# HHO_DRIVE_V1.net
KiCad netlist of a schematic drawn in Altium Designer
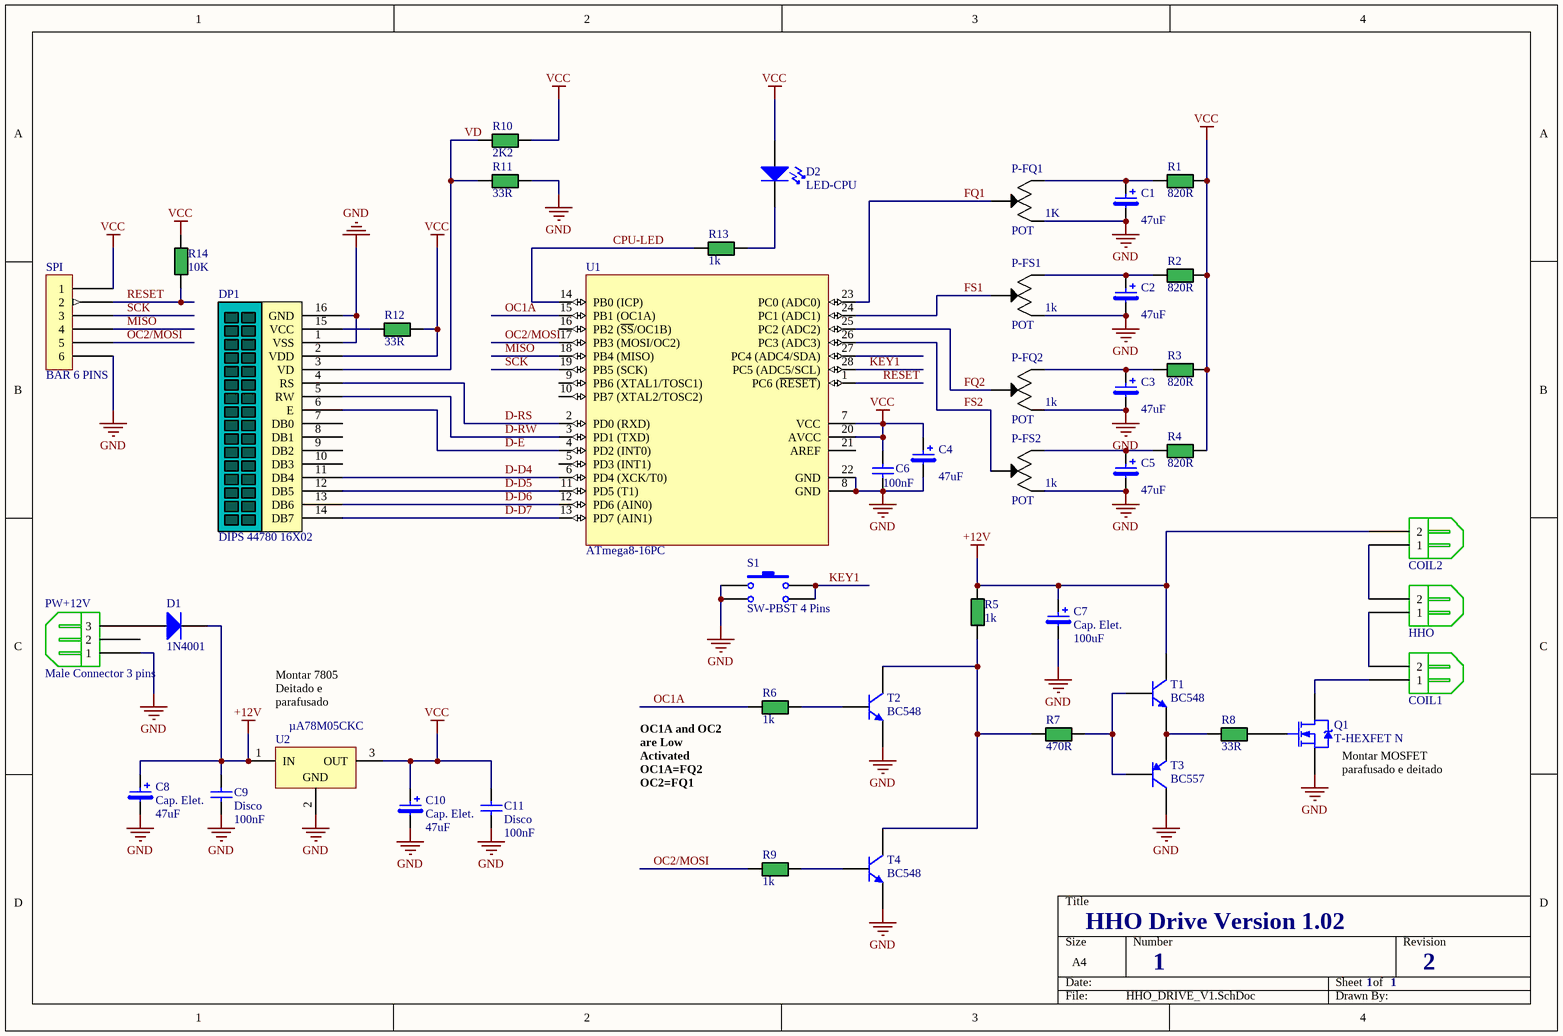
[diagram p0: HHO_DRIVE_V1.SchDoc]

(export (version "E")
  (design (tool "Eeschema 10.0.6"))
  (components
    (comp (ref "C1")
      (value "47uF")
      (footprint "CAP ELE RAD 11mm H")
      (description "Capacitor Radial Eletrolitico")
      (fields (field (name "Comment") "Cap. Elet."))
      (libsource (lib "NEPERMATH") (part "CAP_RADIAL_ELETROLITICO"))
    )
    (comp (ref "C2")
      (value "47uF")
      (footprint "CAP ELE RAD 11mm H")
      (description "Capacitor Radial Eletrolitico")
      (fields (field (name "Comment") "Cap. Elet."))
      (libsource (lib "NEPERMATH") (part "CAP_RADIAL_ELETROLITICO"))
    )
    (comp (ref "C3")
      (value "47uF")
      (footprint "CAP ELE RAD 11mm H")
      (description "Capacitor Radial Eletrolitico")
      (fields (field (name "Comment") "Cap. Elet."))
      (libsource (lib "NEPERMATH") (part "CAP_RADIAL_ELETROLITICO"))
    )
    (comp (ref "C4")
      (value "47uF")
      (footprint "CAP ELE RAD 11mm H")
      (description "Capacitor Radial Eletrolitico")
      (fields (field (name "Comment") "Cap. Elet."))
      (libsource (lib "NEPERMATH") (part "CAP_RADIAL_ELETROLITICO"))
    )
    (comp (ref "C5")
      (value "47uF")
      (footprint "CAP ELE RAD 11mm H")
      (description "Capacitor Radial Eletrolitico")
      (fields (field (name "Comment") "Cap. Elet."))
      (libsource (lib "NEPERMATH") (part "CAP_RADIAL_ELETROLITICO"))
    )
    (comp (ref "C6")
      (value "100nF")
      (footprint "CAP CER DISK 5MM")
      (description "SMD Capacitor 1210 size")
      (fields (field (name "Comment") "Disco"))
      (libsource (lib "NEPERMATH") (part "CAP_DISCO"))
    )
    (comp (ref "C7")
      (value "Cap. Elet.")
      (footprint "CAP ELE RAD 11mm H")
      (description "Capacitor Radial Eletrolitico")
      (fields (field (name "ALTIUM_VALUE") "100uF"))
      (libsource (lib "NEPERMATH") (part "CAP_RADIAL_ELETROLITICO"))
    )
    (comp (ref "C8")
      (value "Cap. Elet.")
      (footprint "CAP ELE RAD 11mm H")
      (description "Capacitor Radial Eletrolitico")
      (fields (field (name "ALTIUM_VALUE") "47uF"))
      (libsource (lib "NEPERMATH") (part "CAP_RADIAL_ELETROLITICO"))
    )
    (comp (ref "C9")
      (value "Disco")
      (footprint "CAP CER DISK 5MM")
      (description "SMD Capacitor 1210 size")
      (fields (field (name "ALTIUM_VALUE") "100nF"))
      (libsource (lib "NEPERMATH") (part "CAP_DISCO"))
    )
    (comp (ref "C10")
      (value "Cap. Elet.")
      (footprint "CAP ELE RAD 11mm H")
      (description "Capacitor Radial Eletrolitico")
      (fields (field (name "ALTIUM_VALUE") "47uF"))
      (libsource (lib "NEPERMATH") (part "CAP_RADIAL_ELETROLITICO"))
    )
    (comp (ref "C11")
      (value "Disco")
      (footprint "CAP CER DISK 5MM")
      (description "SMD Capacitor 1210 size")
      (fields (field (name "ALTIUM_VALUE") "100nF"))
      (libsource (lib "NEPERMATH") (part "CAP_DISCO"))
    )
    (comp (ref "COIL1")
      (value "Male Connector 2 pins")
      (footprint "BR102A")
      (libsource (lib "NEPERMATH") (part "Male Con 2 Pin"))
    )
    (comp (ref "COIL2")
      (value "Male Connector 2 pins")
      (footprint "BR102A")
      (libsource (lib "NEPERMATH") (part "Male Con 2 Pin"))
    )
    (comp (ref "D1")
      (value "1N4001")
      (footprint "DO-41")
      (description "1 Amp General Purpose Rectifier")
      (fields (field (name "PUBLISHER") "Altium Limited"))
      (libsource (lib "NEPERMATH") (part "Diode 1N4001"))
    )
    (comp (ref "D2")
      (value "LED-CPU")
      (footprint "LED Red 3mm")
      (description "LED")
      (libsource (lib "NEPERMATH") (part "LED"))
    )
    (comp (ref "DP1")
      (value "DIPS 44780 16X02")
      (footprint "Display 44780 16x02 com conector")
      (description "Display 44780 16x02 com conector 16 pinos")
      (libsource (lib "NEPERMATH") (part "Display 44780 16x02 com conector 16 pinos"))
    )
    (comp (ref "HHO")
      (value "Male Connector 2 pins")
      (footprint "BR102A")
      (libsource (lib "NEPERMATH") (part "Male Con 2 Pin"))
    )
    (comp (ref "P-FQ1")
      (value "POT")
      (footprint "POT 200MIL/400MIL")
      (description "Potenciometer 3 pins")
      (fields (field (name "ALTIUM_VALUE") "1K"))
      (libsource (lib "NEPERMATH") (part "POT"))
    )
    (comp (ref "P-FQ2")
      (value "POT")
      (footprint "POT 200MIL/400MIL")
      (description "Potenciometer 3 pins")
      (fields (field (name "ALTIUM_VALUE") "1k"))
      (libsource (lib "NEPERMATH") (part "POT"))
    )
    (comp (ref "P-FS1")
      (value "POT")
      (footprint "POT 200MIL/400MIL")
      (description "Potenciometer 3 pins")
      (fields (field (name "ALTIUM_VALUE") "1k"))
      (libsource (lib "NEPERMATH") (part "POT"))
    )
    (comp (ref "P-FS2")
      (value "POT")
      (footprint "POT 200MIL/400MIL")
      (description "Potenciometer 3 pins")
      (fields (field (name "ALTIUM_VALUE") "1k"))
      (libsource (lib "NEPERMATH") (part "POT"))
    )
    (comp (ref "PW+12V")
      (value "Male Connector 3 pins")
      (footprint "BR103A")
      (libsource (lib "NEPERMATH") (part "Male Con 3 Pin"))
    )
    (comp (ref "Q1")
      (value "T-HEXFET N")
      (footprint "TO218 - DEITADO")
      (description "HEXFET Power MOSFET")
      (libsource (lib "NEPERMATH") (part "T-HEXFET N"))
    )
    (comp (ref "R1")
      (value "820R")
      (footprint "RES 300 CR25")
      (description "Generic Resistor")
      (fields (field (name "Comment") "Resistor Generic"))
      (libsource (lib "NEPERMATH") (part "Resistor Generic"))
    )
    (comp (ref "R2")
      (value "820R")
      (footprint "RES 300 CR25")
      (description "Generic Resistor")
      (fields (field (name "Comment") "Resistor Generic"))
      (libsource (lib "NEPERMATH") (part "Resistor Generic"))
    )
    (comp (ref "R3")
      (value "820R")
      (footprint "RES 300 CR25")
      (description "Generic Resistor")
      (fields (field (name "Comment") "Resistor Generic"))
      (libsource (lib "NEPERMATH") (part "Resistor Generic"))
    )
    (comp (ref "R4")
      (value "820R")
      (footprint "RES 300 CR25")
      (description "Generic Resistor")
      (fields (field (name "Comment") "Resistor Generic"))
      (libsource (lib "NEPERMATH") (part "Resistor Generic"))
    )
    (comp (ref "R5")
      (value "1k")
      (footprint "RES 300 CR25")
      (description "Generic Resistor")
      (fields (field (name "Comment") "Resistor Generic"))
      (libsource (lib "") (part "Resistor Generic_1"))
    )
    (comp (ref "R6")
      (value "1k")
      (footprint "RES 300 CR25")
      (description "Generic Resistor")
      (fields (field (name "Comment") "Resistor Generic"))
      (libsource (lib "NEPERMATH") (part "Resistor Generic"))
    )
    (comp (ref "R7")
      (value "470R")
      (footprint "RES 300 CR25")
      (description "Generic Resistor")
      (fields (field (name "Comment") "Resistor Generic"))
      (libsource (lib "NEPERMATH") (part "Resistor Generic"))
    )
    (comp (ref "R8")
      (value "33R")
      (footprint "RES 300 CR25")
      (description "Generic Resistor")
      (fields (field (name "Comment") "Resistor Generic"))
      (libsource (lib "NEPERMATH") (part "Resistor Generic"))
    )
    (comp (ref "R9")
      (value "1k")
      (footprint "RES 300 CR25")
      (description "Generic Resistor")
      (fields (field (name "Comment") "Resistor Generic"))
      (libsource (lib "NEPERMATH") (part "Resistor Generic"))
    )
    (comp (ref "R10")
      (value "2K2")
      (footprint "RES 300 CR25")
      (description "Generic Resistor")
      (fields (field (name "Comment") "Resistor Generic"))
      (libsource (lib "NEPERMATH") (part "Resistor Generic"))
    )
    (comp (ref "R11")
      (value "33R")
      (footprint "RES 300 CR25")
      (description "Generic Resistor")
      (fields (field (name "Comment") "Resistor Generic"))
      (libsource (lib "NEPERMATH") (part "Resistor Generic"))
    )
    (comp (ref "R12")
      (value "33R")
      (footprint "RES 300 CR25")
      (description "Generic Resistor")
      (fields (field (name "Comment") "Resistor Generic"))
      (libsource (lib "NEPERMATH") (part "Resistor Generic"))
    )
    (comp (ref "R13")
      (value "1k")
      (footprint "RES 300 CR25")
      (description "Generic Resistor")
      (fields (field (name "Comment") "Resistor Generic"))
      (libsource (lib "NEPERMATH") (part "Resistor Generic"))
    )
    (comp (ref "R14")
      (value "10K")
      (footprint "RES 300 CR25")
      (description "Generic Resistor")
      (fields (field (name "Comment") "Resistor Generic"))
      (libsource (lib "") (part "Resistor Generic_1"))
    )
    (comp (ref "S1")
      (value "SW-PBST 4 Pins")
      (footprint "SW-PBST 4 Pins - SKHH 17 mm")
      (fields (field (name "PUBLISHER") "Altium Limited"))
      (libsource (lib "NEPERMATH") (part "SW-PBST 4 Pins SKHH"))
    )
    (comp (ref "SPI")
      (value "BAR 6 PINS")
      (footprint "HEADER BAR 6 PINS")
      (description ".100 Inch AMPMODU Headers 1-826629-0 (Tyco)")
      (libsource (lib "NEPERMATH") (part "HEADER BAR  6 PINS"))
    )
    (comp (ref "T1")
      (value "BC548")
      (footprint "TO-92 - Large")
      (description "General Bipolar Transistor NPN")
      (fields (field (name "Comment") "Transistor"))
      (libsource (lib "NEPERMATH") (part "T-NPN"))
    )
    (comp (ref "T2")
      (value "BC548")
      (footprint "TO-92 - Large")
      (description "General Bipolar Transistor NPN")
      (fields (field (name "Comment") "Transistor"))
      (libsource (lib "NEPERMATH") (part "T-NPN"))
    )
    (comp (ref "T3")
      (value "BC557")
      (footprint "TO-92 - Large")
      (description "General Bipolar Transistor NPN")
      (fields (field (name "Comment") "Transistor"))
      (libsource (lib "NEPERMATH") (part "T-PNP"))
    )
    (comp (ref "T4")
      (value "BC548")
      (footprint "TO-92 - Large")
      (description "General Bipolar Transistor NPN")
      (fields (field (name "Comment") "Transistor"))
      (libsource (lib "NEPERMATH") (part "T-NPN"))
    )
    (comp (ref "U1")
      (value "ATmega8-16PC")
      (footprint "28P3")
      (description "8-Bit AVR Microcontroller with 8K Bytes of In-System Programmable Flash Memory")
      (libsource (lib "NEPERMATH") (part "ATmega8-16PC"))
    )
    (comp (ref "U2")
      (value "µA78M05CKC")
      (footprint "KC03 - Deitado")
      (description "Positive-Voltage Regulator")
      (fields (field (name "PUBLISHER") "Altium Limited"))
      (libsource (lib "NEPERMATH") (part "µA78M05CKC"))
    )
  )
  (nets
    (net (code "1") (name "+12V") (class "Default")
      (node (ref "C7") (pin "1") (pinfunction "1_1") (pintype "passive"))
      (node (ref "C8") (pin "1") (pinfunction "1_1") (pintype "passive"))
      (node (ref "C9") (pin "2") (pinfunction "2_2") (pintype "passive"))
      (node (ref "COIL2") (pin "2") (pinfunction "2_2") (pintype "passive"))
      (node (ref "D1") (pin "2") (pinfunction "K_2") (pintype "passive"))
      (node (ref "R5") (pin "2") (pinfunction "2_2") (pintype "passive"))
      (node (ref "T1") (pin "3") (pinfunction "C_3") (pintype "passive"))
      (node (ref "U2") (pin "1") (pinfunction "IN_1") (pintype "power_in"))
    )
    (net (code "2") (name "/CPU-LED") (class "Default")
      (node (ref "R13") (pin "1") (pinfunction "1_1") (pintype "passive"))
      (node (ref "U1") (pin "14") (pinfunction "PB0_(ICP)_14") (pintype "bidirectional"))
    )
    (net (code "3") (name "/D-D4") (class "Default")
      (node (ref "DP1") (pin "11") (pinfunction "DB4_11") (pintype "passive"))
      (node (ref "U1") (pin "6") (pinfunction "PD4_(XCK/T0)_6") (pintype "bidirectional"))
    )
    (net (code "4") (name "/D-D5") (class "Default")
      (node (ref "DP1") (pin "12") (pinfunction "DB5_12") (pintype "passive"))
      (node (ref "U1") (pin "11") (pinfunction "PD5_(T1)_11") (pintype "bidirectional"))
    )
    (net (code "5") (name "/D-D6") (class "Default")
      (node (ref "DP1") (pin "13") (pinfunction "DB6_13") (pintype "passive"))
      (node (ref "U1") (pin "12") (pinfunction "PD6_(AIN0)_12") (pintype "bidirectional"))
    )
    (net (code "6") (name "/D-D7") (class "Default")
      (node (ref "DP1") (pin "14") (pinfunction "DB7_14") (pintype "passive"))
      (node (ref "U1") (pin "13") (pinfunction "PD7_(AIN1)_13") (pintype "bidirectional"))
    )
    (net (code "7") (name "/D-E") (class "Default")
      (node (ref "DP1") (pin "6") (pinfunction "E_6") (pintype "passive"))
      (node (ref "U1") (pin "4") (pinfunction "PD2_(INT0)_4") (pintype "bidirectional"))
    )
    (net (code "8") (name "/D-RS") (class "Default")
      (node (ref "DP1") (pin "4") (pinfunction "RS_4") (pintype "passive"))
      (node (ref "U1") (pin "2") (pinfunction "PD0_(RXD)_2") (pintype "bidirectional"))
    )
    (net (code "9") (name "/D-RW") (class "Default")
      (node (ref "DP1") (pin "5") (pinfunction "RW_5") (pintype "passive"))
      (node (ref "U1") (pin "3") (pinfunction "PD1_(TXD)_3") (pintype "bidirectional"))
    )
    (net (code "10") (name "/FQ1") (class "Default")
      (node (ref "P-FQ1") (pin "2") (pinfunction "2_2") (pintype "passive"))
      (node (ref "U1") (pin "23") (pinfunction "PC0_(ADC0)_23") (pintype "bidirectional"))
    )
    (net (code "11") (name "/FQ2") (class "Default")
      (node (ref "P-FQ2") (pin "2") (pinfunction "2_2") (pintype "passive"))
      (node (ref "U1") (pin "25") (pinfunction "PC2_(ADC2)_25") (pintype "bidirectional"))
    )
    (net (code "12") (name "/FS1") (class "Default")
      (node (ref "P-FS1") (pin "2") (pinfunction "2_2") (pintype "passive"))
      (node (ref "U1") (pin "24") (pinfunction "PC1_(ADC1)_24") (pintype "bidirectional"))
    )
    (net (code "13") (name "/FS2") (class "Default")
      (node (ref "P-FS2") (pin "2") (pinfunction "2_2") (pintype "passive"))
      (node (ref "U1") (pin "26") (pinfunction "PC3_(ADC3)_26") (pintype "bidirectional"))
    )
    (net (code "14") (name "/KEY1") (class "Default")
      (node (ref "S1") (pin "3") (pinfunction "3_3") (pintype "passive"))
      (node (ref "S1") (pin "4") (pinfunction "4_4") (pintype "passive"))
      (node (ref "U1") (pin "28") (pinfunction "PC5_(ADC5/SCL)_28") (pintype "bidirectional"))
    )
    (net (code "15") (name "/MISO") (class "Default")
      (node (ref "SPI") (pin "4") (pinfunction "4_4") (pintype "passive"))
      (node (ref "U1") (pin "18") (pinfunction "PB4_(MISO)_18") (pintype "bidirectional"))
    )
    (net (code "16") (name "/OC1A") (class "Default")
      (node (ref "R6") (pin "1") (pinfunction "1_1") (pintype "passive"))
      (node (ref "U1") (pin "15") (pinfunction "PB1_(OC1A)_15") (pintype "bidirectional"))
    )
    (net (code "17") (name "/OC2{slash}MOSI") (class "Default")
      (node (ref "R9") (pin "1") (pinfunction "1_1") (pintype "passive"))
      (node (ref "SPI") (pin "5") (pinfunction "5_5") (pintype "passive"))
      (node (ref "U1") (pin "17") (pinfunction "PB3_(MOSI/OC2)_17") (pintype "bidirectional"))
    )
    (net (code "18") (name "/RESET") (class "Default")
      (node (ref "R14") (pin "1") (pinfunction "1_1") (pintype "passive"))
      (node (ref "SPI") (pin "2") (pinfunction "2_2") (pintype "output"))
      (node (ref "U1") (pin "1") (pinfunction "PC6_(~{RESET})_1") (pintype "bidirectional"))
    )
    (net (code "19") (name "/SCK") (class "Default")
      (node (ref "SPI") (pin "3") (pinfunction "3_3") (pintype "passive"))
      (node (ref "U1") (pin "19") (pinfunction "PB5_(SCK)_19") (pintype "bidirectional"))
    )
    (net (code "20") (name "/VD") (class "Default")
      (node (ref "DP1") (pin "3") (pinfunction "VD_3") (pintype "passive"))
      (node (ref "R10") (pin "1") (pinfunction "1_1") (pintype "passive"))
      (node (ref "R11") (pin "1") (pinfunction "1_1") (pintype "passive"))
    )
    (net (code "21") (name "GND") (class "Default")
      (node (ref "C1") (pin "2") (pinfunction "2_2") (pintype "passive"))
      (node (ref "C10") (pin "2") (pinfunction "2_2") (pintype "passive"))
      (node (ref "C11") (pin "1") (pinfunction "1_1") (pintype "passive"))
      (node (ref "C2") (pin "2") (pinfunction "2_2") (pintype "passive"))
      (node (ref "C3") (pin "2") (pinfunction "2_2") (pintype "passive"))
      (node (ref "C4") (pin "2") (pinfunction "2_2") (pintype "passive"))
      (node (ref "C5") (pin "2") (pinfunction "2_2") (pintype "passive"))
      (node (ref "C6") (pin "1") (pinfunction "1_1") (pintype "passive"))
      (node (ref "C7") (pin "2") (pinfunction "2_2") (pintype "passive"))
      (node (ref "C8") (pin "2") (pinfunction "2_2") (pintype "passive"))
      (node (ref "C9") (pin "1") (pinfunction "1_1") (pintype "passive"))
      (node (ref "DP1") (pin "1") (pinfunction "VSS_1") (pintype "power_in"))
      (node (ref "DP1") (pin "16") (pinfunction "GND_16") (pintype "power_in"))
      (node (ref "P-FQ1") (pin "1") (pinfunction "1_1") (pintype "passive"))
      (node (ref "P-FQ2") (pin "1") (pinfunction "1_1") (pintype "passive"))
      (node (ref "P-FS1") (pin "1") (pinfunction "1_1") (pintype "passive"))
      (node (ref "P-FS2") (pin "1") (pinfunction "1_1") (pintype "passive"))
      (node (ref "PW+12V") (pin "1") (pinfunction "1_1") (pintype "passive"))
      (node (ref "Q1") (pin "3") (pinfunction "S_3") (pintype "passive"))
      (node (ref "R11") (pin "2") (pinfunction "2_2") (pintype "passive"))
      (node (ref "S1") (pin "1") (pinfunction "1_1") (pintype "passive"))
      (node (ref "S1") (pin "2") (pinfunction "2_2") (pintype "passive"))
      (node (ref "SPI") (pin "6") (pinfunction "6_6") (pintype "passive"))
      (node (ref "T2") (pin "1") (pinfunction "E_1") (pintype "passive"))
      (node (ref "T3") (pin "3") (pinfunction "C_3") (pintype "passive"))
      (node (ref "T4") (pin "1") (pinfunction "E_1") (pintype "passive"))
      (node (ref "U1") (pin "22") (pinfunction "GND_22") (pintype "power_in"))
      (node (ref "U1") (pin "8") (pinfunction "GND_8") (pintype "power_in"))
      (node (ref "U2") (pin "2") (pinfunction "GND_2") (pintype "power_in"))
    )
    (net (code "22") (name "Net-(C1-Pad1)") (class "Default")
      (node (ref "C1") (pin "1") (pinfunction "1_1") (pintype "passive"))
      (node (ref "P-FQ1") (pin "3") (pinfunction "3_3") (pintype "passive"))
      (node (ref "R1") (pin "1") (pinfunction "1_1") (pintype "passive"))
    )
    (net (code "23") (name "Net-(C2-Pad1)") (class "Default")
      (node (ref "C2") (pin "1") (pinfunction "1_1") (pintype "passive"))
      (node (ref "P-FS1") (pin "3") (pinfunction "3_3") (pintype "passive"))
      (node (ref "R2") (pin "1") (pinfunction "1_1") (pintype "passive"))
    )
    (net (code "24") (name "Net-(C3-Pad1)") (class "Default")
      (node (ref "C3") (pin "1") (pinfunction "1_1") (pintype "passive"))
      (node (ref "P-FQ2") (pin "3") (pinfunction "3_3") (pintype "passive"))
      (node (ref "R3") (pin "1") (pinfunction "1_1") (pintype "passive"))
    )
    (net (code "25") (name "Net-(C5-Pad1)") (class "Default")
      (node (ref "C5") (pin "1") (pinfunction "1_1") (pintype "passive"))
      (node (ref "P-FS2") (pin "3") (pinfunction "3_3") (pintype "passive"))
      (node (ref "R4") (pin "1") (pinfunction "1_1") (pintype "passive"))
    )
    (net (code "26") (name "Net-(COIL1-Pad2)") (class "Default")
      (node (ref "COIL1") (pin "2") (pinfunction "2_2") (pintype "passive"))
      (node (ref "HHO") (pin "1") (pinfunction "1_1") (pintype "passive"))
    )
    (net (code "27") (name "Net-(COIL2-Pad1)") (class "Default")
      (node (ref "COIL2") (pin "1") (pinfunction "1_1") (pintype "passive"))
      (node (ref "HHO") (pin "2") (pinfunction "2_2") (pintype "passive"))
    )
    (net (code "28") (name "Net-(D1-A)") (class "Default")
      (node (ref "D1") (pin "1") (pinfunction "A_1") (pintype "passive"))
      (node (ref "PW+12V") (pin "3") (pinfunction "3_3") (pintype "passive"))
    )
    (net (code "29") (name "Net-(D2-PadK)") (class "Default")
      (node (ref "D2") (pin "K") (pinfunction "K_K") (pintype "passive"))
      (node (ref "R13") (pin "2") (pinfunction "2_2") (pintype "passive"))
    )
    (net (code "30") (name "Net-(DP1-VCC)") (class "Default")
      (node (ref "DP1") (pin "15") (pinfunction "VCC_15") (pintype "power_in"))
      (node (ref "R12") (pin "1") (pinfunction "1_1") (pintype "passive"))
    )
    (net (code "31") (name "Net-(Q1-D)") (class "Default")
      (node (ref "COIL1") (pin "1") (pinfunction "1_1") (pintype "passive"))
      (node (ref "Q1") (pin "2") (pinfunction "D_2") (pintype "passive"))
    )
    (net (code "32") (name "Net-(Q1-G)") (class "Default")
      (node (ref "Q1") (pin "1") (pinfunction "G_1") (pintype "passive"))
      (node (ref "R8") (pin "2") (pinfunction "2_2") (pintype "passive"))
    )
    (net (code "33") (name "Net-(T1-B)") (class "Default")
      (node (ref "R7") (pin "2") (pinfunction "2_2") (pintype "passive"))
      (node (ref "T1") (pin "2") (pinfunction "B_2") (pintype "passive"))
      (node (ref "T3") (pin "2") (pinfunction "B_2") (pintype "passive"))
    )
    (net (code "34") (name "Net-(T1-E)") (class "Default")
      (node (ref "R8") (pin "1") (pinfunction "1_1") (pintype "passive"))
      (node (ref "T1") (pin "1") (pinfunction "E_1") (pintype "passive"))
      (node (ref "T3") (pin "1") (pinfunction "E_1") (pintype "passive"))
    )
    (net (code "35") (name "Net-(T2-B)") (class "Default")
      (node (ref "R6") (pin "2") (pinfunction "2_2") (pintype "passive"))
      (node (ref "T2") (pin "2") (pinfunction "B_2") (pintype "passive"))
    )
    (net (code "36") (name "Net-(T2-C)") (class "Default")
      (node (ref "R5") (pin "1") (pinfunction "1_1") (pintype "passive"))
      (node (ref "R7") (pin "1") (pinfunction "1_1") (pintype "passive"))
      (node (ref "T2") (pin "3") (pinfunction "C_3") (pintype "passive"))
      (node (ref "T4") (pin "3") (pinfunction "C_3") (pintype "passive"))
    )
    (net (code "37") (name "Net-(T4-B)") (class "Default")
      (node (ref "R9") (pin "2") (pinfunction "2_2") (pintype "passive"))
      (node (ref "T4") (pin "2") (pinfunction "B_2") (pintype "passive"))
    )
    (net (code "38") (name "VCC") (class "Default")
      (node (ref "C10") (pin "1") (pinfunction "1_1") (pintype "passive"))
      (node (ref "C11") (pin "2") (pinfunction "2_2") (pintype "passive"))
      (node (ref "C4") (pin "1") (pinfunction "1_1") (pintype "passive"))
      (node (ref "C6") (pin "2") (pinfunction "2_2") (pintype "passive"))
      (node (ref "D2") (pin "A") (pinfunction "A_A") (pintype "passive"))
      (node (ref "DP1") (pin "2") (pinfunction "VDD_2") (pintype "power_in"))
      (node (ref "R1") (pin "2") (pinfunction "2_2") (pintype "passive"))
      (node (ref "R10") (pin "2") (pinfunction "2_2") (pintype "passive"))
      (node (ref "R12") (pin "2") (pinfunction "2_2") (pintype "passive"))
      (node (ref "R14") (pin "2") (pinfunction "2_2") (pintype "passive"))
      (node (ref "R2") (pin "2") (pinfunction "2_2") (pintype "passive"))
      (node (ref "R3") (pin "2") (pinfunction "2_2") (pintype "passive"))
      (node (ref "R4") (pin "2") (pinfunction "2_2") (pintype "passive"))
      (node (ref "SPI") (pin "1") (pinfunction "1_1") (pintype "passive"))
      (node (ref "U1") (pin "20") (pinfunction "AVCC_20") (pintype "power_in"))
      (node (ref "U1") (pin "7") (pinfunction "VCC_7") (pintype "power_in"))
      (node (ref "U2") (pin "3") (pinfunction "OUT_3") (pintype "power_in"))
    )
    (net (code "39") (name "unconnected-(DP1-DB0-Pad7)") (class "Default")
      (node (ref "DP1") (pin "7") (pinfunction "DB0_7") (pintype "passive"))
    )
    (net (code "40") (name "unconnected-(DP1-DB1-Pad8)") (class "Default")
      (node (ref "DP1") (pin "8") (pinfunction "DB1_8") (pintype "passive"))
    )
    (net (code "41") (name "unconnected-(DP1-DB2-Pad9)") (class "Default")
      (node (ref "DP1") (pin "9") (pinfunction "DB2_9") (pintype "passive"))
    )
    (net (code "42") (name "unconnected-(DP1-DB3-Pad10)") (class "Default")
      (node (ref "DP1") (pin "10") (pinfunction "DB3_10") (pintype "passive"))
    )
    (net (code "43") (name "unconnected-(PW+12V-Pad2)") (class "Default")
      (node (ref "PW+12V") (pin "2") (pinfunction "2_2") (pintype "passive"))
    )
    (net (code "44") (name "unconnected-(U1-AREF-Pad21)") (class "Default")
      (node (ref "U1") (pin "21") (pinfunction "AREF_21") (pintype "passive"))
    )
    (net (code "45") (name "unconnected-(U1-PB2_(~{SS}{slash}OC1B)-Pad16)") (class "Default")
      (node (ref "U1") (pin "16") (pinfunction "PB2_(~{SS}/OC1B)_16") (pintype "bidirectional"))
    )
    (net (code "46") (name "unconnected-(U1-PB6_(XTAL1{slash}TOSC1)-Pad9)") (class "Default")
      (node (ref "U1") (pin "9") (pinfunction "PB6_(XTAL1/TOSC1)_9") (pintype "bidirectional"))
    )
    (net (code "47") (name "unconnected-(U1-PB7_(XTAL2{slash}TOSC2)-Pad10)") (class "Default")
      (node (ref "U1") (pin "10") (pinfunction "PB7_(XTAL2/TOSC2)_10") (pintype "bidirectional"))
    )
    (net (code "48") (name "unconnected-(U1-PC4_(ADC4{slash}SDA)-Pad27)") (class "Default")
      (node (ref "U1") (pin "27") (pinfunction "PC4_(ADC4/SDA)_27") (pintype "bidirectional"))
    )
    (net (code "49") (name "unconnected-(U1-PD3_(INT1)-Pad5)") (class "Default")
      (node (ref "U1") (pin "5") (pinfunction "PD3_(INT1)_5") (pintype "bidirectional"))
    )
  )
)
